# led_board.net
KiCad netlist of a schematic drawn in EAGLE
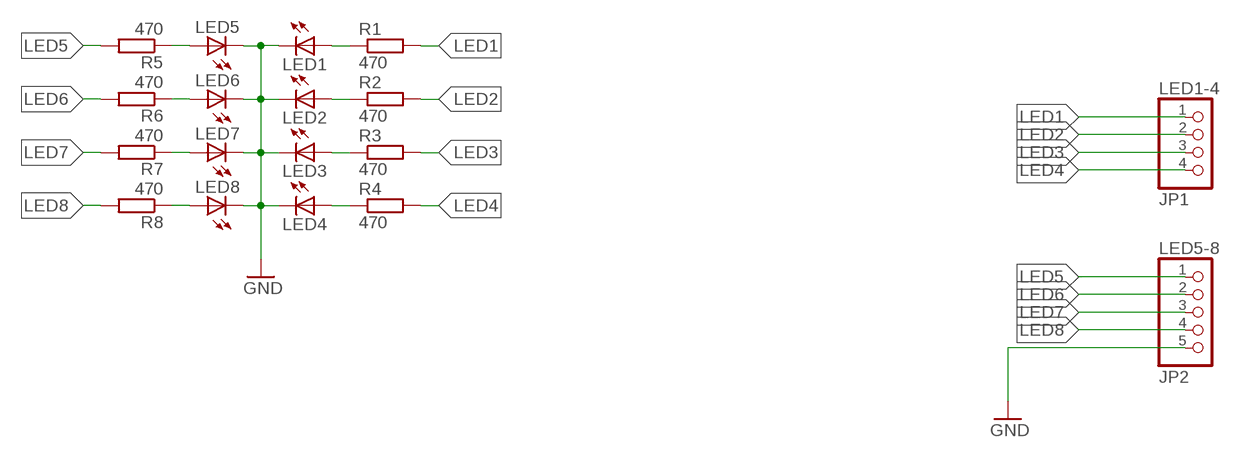
[diagram p0: schematic, sheet 1]

(export (version "E")
  (design (tool "Eeschema 10.0.6"))
  (components
    (comp (ref "LED1")
      (value "LED3MM")
      (footprint "eagle-import:LED3MM")
      (libsource (lib "eagle-import") (part "LED3MM"))
    )
    (comp (ref "LED1-4")
      (value "JP1")
      (footprint "eagle-import:1X04")
      (libsource (lib "eagle-import") (part "PINHD-1X4"))
    )
    (comp (ref "LED2")
      (value "LED3MM")
      (footprint "eagle-import:LED3MM")
      (libsource (lib "eagle-import") (part "LED3MM"))
    )
    (comp (ref "LED3")
      (value "LED3MM")
      (footprint "eagle-import:LED3MM")
      (libsource (lib "eagle-import") (part "LED3MM"))
    )
    (comp (ref "LED4")
      (value "LED3MM")
      (footprint "eagle-import:LED3MM")
      (libsource (lib "eagle-import") (part "LED3MM"))
    )
    (comp (ref "LED5")
      (value "LED3MM")
      (footprint "eagle-import:LED3MM")
      (libsource (lib "eagle-import") (part "LED3MM"))
    )
    (comp (ref "LED5-8")
      (value "JP2")
      (footprint "eagle-import:1X05")
      (libsource (lib "eagle-import") (part "PINHD-1X5"))
    )
    (comp (ref "LED6")
      (value "LED3MM")
      (footprint "eagle-import:LED3MM")
      (libsource (lib "eagle-import") (part "LED3MM"))
    )
    (comp (ref "LED7")
      (value "LED3MM")
      (footprint "eagle-import:LED3MM")
      (libsource (lib "eagle-import") (part "LED3MM"))
    )
    (comp (ref "LED8")
      (value "LED3MM")
      (footprint "eagle-import:LED3MM")
      (libsource (lib "eagle-import") (part "LED3MM"))
    )
    (comp (ref "R1")
      (value "470")
      (footprint "eagle-import:R0805")
      (libsource (lib "eagle-import") (part "R-EU_R0805"))
    )
    (comp (ref "R2")
      (value "470")
      (footprint "eagle-import:R0805")
      (libsource (lib "eagle-import") (part "R-EU_R0805"))
    )
    (comp (ref "R3")
      (value "470")
      (footprint "eagle-import:R0805")
      (libsource (lib "eagle-import") (part "R-EU_R0805"))
    )
    (comp (ref "R4")
      (value "470")
      (footprint "eagle-import:R0805")
      (libsource (lib "eagle-import") (part "R-EU_R0805"))
    )
    (comp (ref "R5")
      (value "470")
      (footprint "eagle-import:R0805")
      (libsource (lib "eagle-import") (part "R-EU_R0805"))
    )
    (comp (ref "R6")
      (value "470")
      (footprint "eagle-import:R0805")
      (libsource (lib "eagle-import") (part "R-EU_R0805"))
    )
    (comp (ref "R7")
      (value "470")
      (footprint "eagle-import:R0805")
      (libsource (lib "eagle-import") (part "R-EU_R0805"))
    )
    (comp (ref "R8")
      (value "470")
      (footprint "eagle-import:R0805")
      (libsource (lib "eagle-import") (part "R-EU_R0805"))
    )
  )
  (nets
    (net (code "1") (name "GND") (class "Default")
      (node (ref "LED1") (pin "K") (pinfunction "C_K") (pintype "passive"))
      (node (ref "LED2") (pin "K") (pinfunction "C_K") (pintype "passive"))
      (node (ref "LED3") (pin "K") (pinfunction "C_K") (pintype "passive"))
      (node (ref "LED4") (pin "K") (pinfunction "C_K") (pintype "passive"))
      (node (ref "LED5") (pin "K") (pinfunction "C_K") (pintype "passive"))
      (node (ref "LED5-8") (pin "5") (pinfunction "5_5") (pintype "passive"))
      (node (ref "LED6") (pin "K") (pinfunction "C_K") (pintype "passive"))
      (node (ref "LED7") (pin "K") (pinfunction "C_K") (pintype "passive"))
      (node (ref "LED8") (pin "K") (pinfunction "C_K") (pintype "passive"))
    )
    (net (code "2") (name "LED1") (class "Default")
      (node (ref "LED1-4") (pin "1") (pinfunction "1_1") (pintype "passive"))
      (node (ref "R1") (pin "2") (pinfunction "2_2") (pintype "passive"))
    )
    (net (code "3") (name "LED2") (class "Default")
      (node (ref "LED1-4") (pin "2") (pinfunction "2_2") (pintype "passive"))
      (node (ref "R2") (pin "2") (pinfunction "2_2") (pintype "passive"))
    )
    (net (code "4") (name "LED3") (class "Default")
      (node (ref "LED1-4") (pin "3") (pinfunction "3_3") (pintype "passive"))
      (node (ref "R3") (pin "2") (pinfunction "2_2") (pintype "passive"))
    )
    (net (code "5") (name "LED4") (class "Default")
      (node (ref "LED1-4") (pin "4") (pinfunction "4_4") (pintype "passive"))
      (node (ref "R4") (pin "2") (pinfunction "2_2") (pintype "passive"))
    )
    (net (code "6") (name "LED5") (class "Default")
      (node (ref "LED5-8") (pin "1") (pinfunction "1_1") (pintype "passive"))
      (node (ref "R5") (pin "2") (pinfunction "2_2") (pintype "passive"))
    )
    (net (code "7") (name "LED6") (class "Default")
      (node (ref "LED5-8") (pin "2") (pinfunction "2_2") (pintype "passive"))
      (node (ref "R6") (pin "2") (pinfunction "2_2") (pintype "passive"))
    )
    (net (code "8") (name "LED7") (class "Default")
      (node (ref "LED5-8") (pin "3") (pinfunction "3_3") (pintype "passive"))
      (node (ref "R7") (pin "2") (pinfunction "2_2") (pintype "passive"))
    )
    (net (code "9") (name "LED8") (class "Default")
      (node (ref "LED5-8") (pin "4") (pinfunction "4_4") (pintype "passive"))
      (node (ref "R8") (pin "2") (pinfunction "2_2") (pintype "passive"))
    )
    (net (code "10") (name "Net-(LED1-PadA)") (class "Default")
      (node (ref "LED1") (pin "A") (pinfunction "A_A") (pintype "passive"))
      (node (ref "R1") (pin "1") (pinfunction "1_1") (pintype "passive"))
    )
    (net (code "11") (name "Net-(LED2-PadA)") (class "Default")
      (node (ref "LED2") (pin "A") (pinfunction "A_A") (pintype "passive"))
      (node (ref "R2") (pin "1") (pinfunction "1_1") (pintype "passive"))
    )
    (net (code "12") (name "Net-(LED3-PadA)") (class "Default")
      (node (ref "LED3") (pin "A") (pinfunction "A_A") (pintype "passive"))
      (node (ref "R3") (pin "1") (pinfunction "1_1") (pintype "passive"))
    )
    (net (code "13") (name "Net-(LED4-PadA)") (class "Default")
      (node (ref "LED4") (pin "A") (pinfunction "A_A") (pintype "passive"))
      (node (ref "R4") (pin "1") (pinfunction "1_1") (pintype "passive"))
    )
    (net (code "14") (name "Net-(LED5-PadA)") (class "Default")
      (node (ref "LED5") (pin "A") (pinfunction "A_A") (pintype "passive"))
      (node (ref "R5") (pin "1") (pinfunction "1_1") (pintype "passive"))
    )
    (net (code "15") (name "Net-(LED6-PadA)") (class "Default")
      (node (ref "LED6") (pin "A") (pinfunction "A_A") (pintype "passive"))
      (node (ref "R6") (pin "1") (pinfunction "1_1") (pintype "passive"))
    )
    (net (code "16") (name "Net-(LED7-PadA)") (class "Default")
      (node (ref "LED7") (pin "A") (pinfunction "A_A") (pintype "passive"))
      (node (ref "R7") (pin "1") (pinfunction "1_1") (pintype "passive"))
    )
    (net (code "17") (name "Net-(LED8-PadA)") (class "Default")
      (node (ref "LED8") (pin "A") (pinfunction "A_A") (pintype "passive"))
      (node (ref "R8") (pin "1") (pinfunction "1_1") (pintype "passive"))
    )
  )
)
